# lm3414-rgb-ca-led-driver-mk-1_0.net
KiCad netlist of a schematic drawn in EAGLE
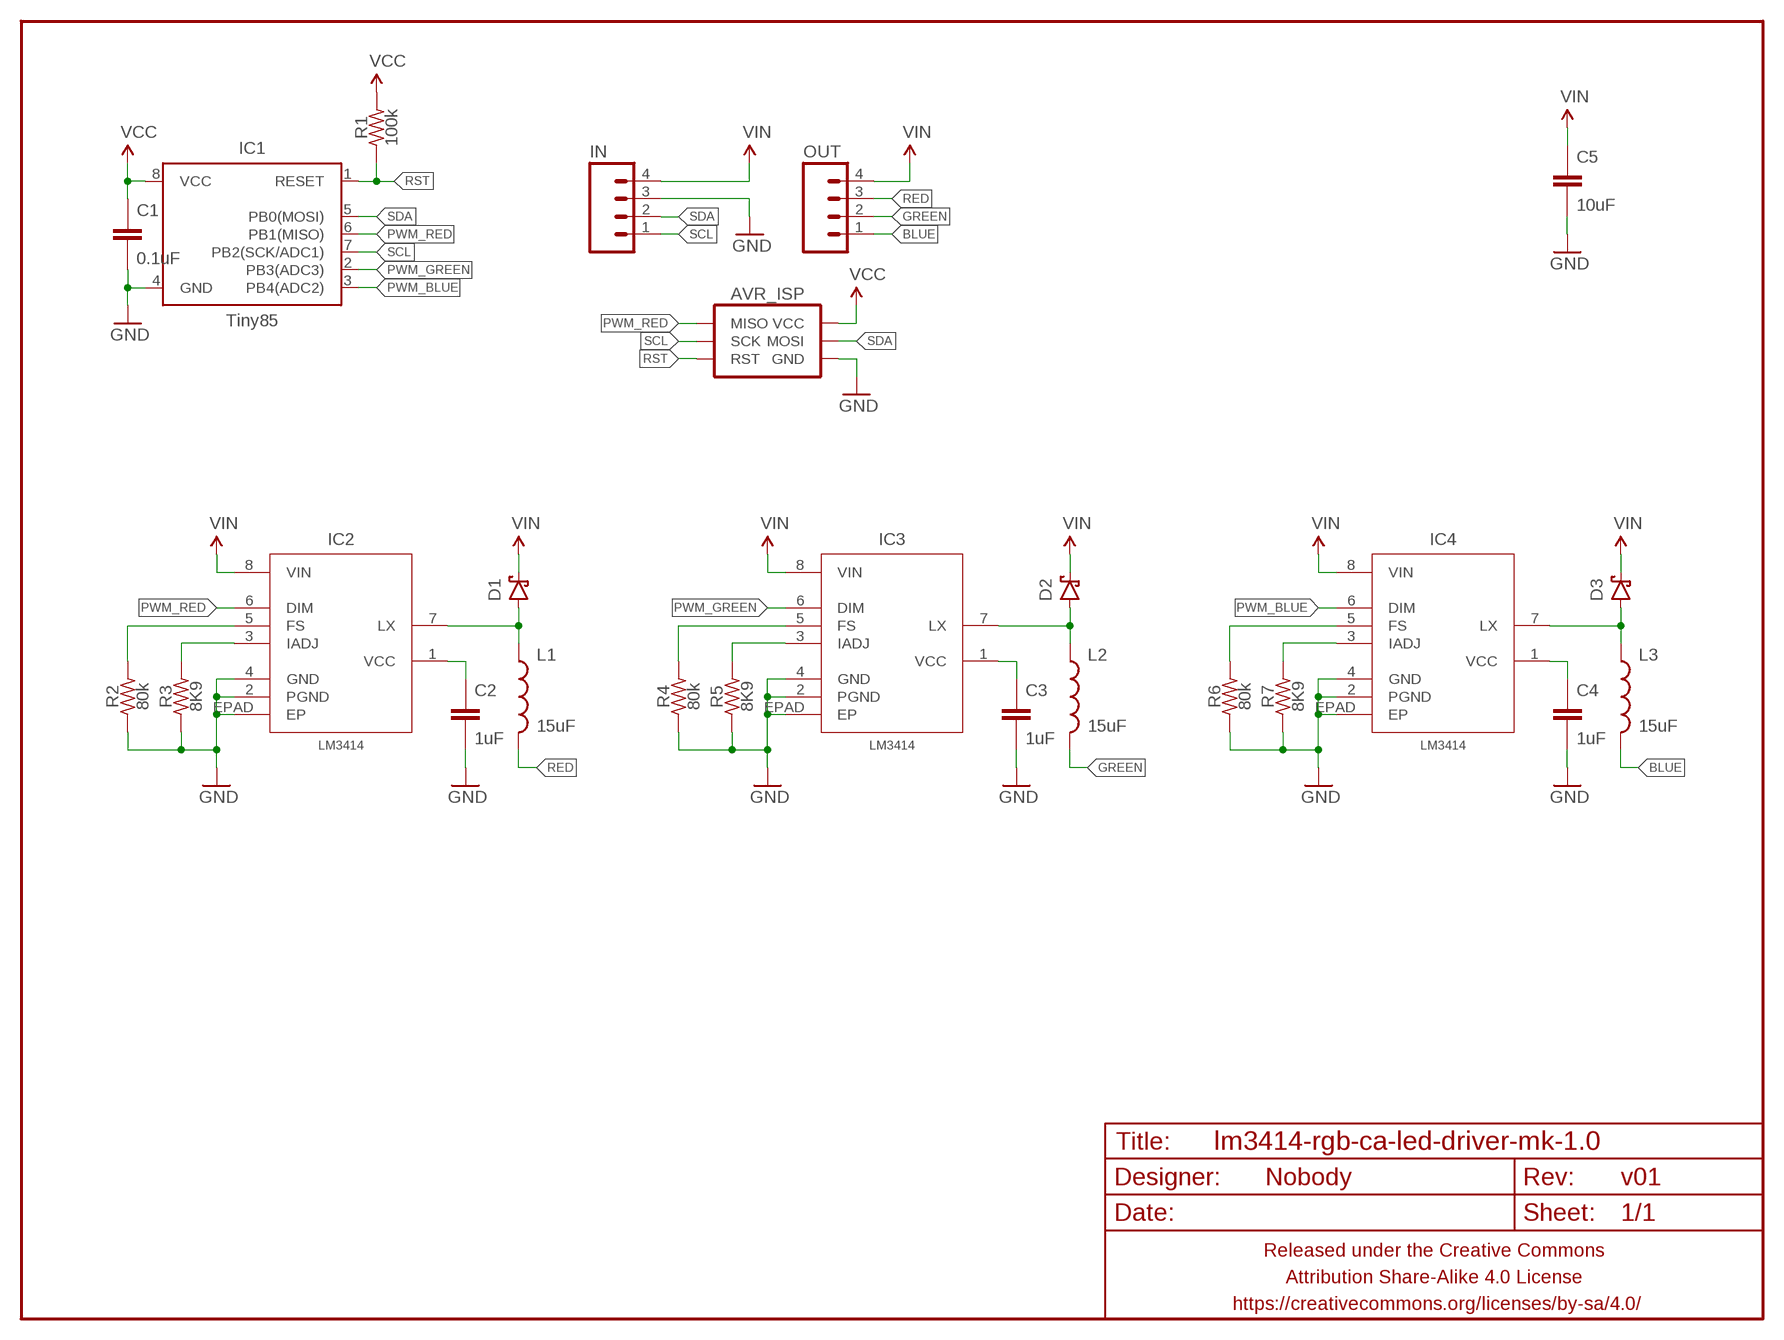
[diagram p0: schematic, sheet 1]

(export (version "E")
  (design (tool "Eeschema 10.0.6"))
  (components
    (comp (ref "AVR_ISP")
      (value "AVR_SPI_PRG_6TESTPOINTS")
      (footprint "eagle-import:2X3_TEST_POINTS")
      (libsource (lib "eagle-import") (part "AVR_SPI_PRG_6TESTPOINTS"))
    )
    (comp (ref "C1")
      (value "0.1uF")
      (footprint "eagle-import:C0603")
      (libsource (lib "eagle-import") (part "CAPACITOR-CERAMICC0603"))
    )
    (comp (ref "C2")
      (value "1uF")
      (footprint "eagle-import:C0603")
      (libsource (lib "eagle-import") (part "CAPACITOR-CERAMICC0603"))
    )
    (comp (ref "C3")
      (value "1uF")
      (footprint "eagle-import:C0603")
      (libsource (lib "eagle-import") (part "CAPACITOR-CERAMICC0603"))
    )
    (comp (ref "C4")
      (value "1uF")
      (footprint "eagle-import:C0603")
      (libsource (lib "eagle-import") (part "CAPACITOR-CERAMICC0603"))
    )
    (comp (ref "C5")
      (value "10uF")
      (footprint "eagle-import:C1206")
      (libsource (lib "eagle-import") (part "CAPACITOR-CERAMICC1206"))
    )
    (comp (ref "D1")
      (value "DIODE-SCHOTTKYSMA")
      (footprint "eagle-import:SMA-DIODE-SCHOTTKY")
      (libsource (lib "eagle-import") (part "DIODE-SCHOTTKYSMA"))
    )
    (comp (ref "D2")
      (value "DIODE-SCHOTTKYSMA")
      (footprint "eagle-import:SMA-DIODE-SCHOTTKY")
      (libsource (lib "eagle-import") (part "DIODE-SCHOTTKYSMA"))
    )
    (comp (ref "D3")
      (value "DIODE-SCHOTTKYSMA")
      (footprint "eagle-import:SMA-DIODE-SCHOTTKY")
      (libsource (lib "eagle-import") (part "DIODE-SCHOTTKYSMA"))
    )
    (comp (ref "FRAME1")
      (value "FRAME-LETTERNO_PACKAGE")
      (footprint "eagle-import:DUMMY")
      (fields (field (name "DESIGNER") "Nobody"))
      (libsource (lib "eagle-import") (part "FRAME-LETTERNO_PACKAGE"))
    )
    (comp (ref "IC1")
      (value "Tiny85")
      (footprint "eagle-import:SO08-EIAJ")
      (libsource (lib "eagle-import") (part "ATTINY45TINY85-20-SOICW"))
    )
    (comp (ref "IC2")
      (value "LM3414")
      (footprint "eagle-import:SO08-PAD")
      (libsource (lib "eagle-import") (part "LM3414SO08-PAD"))
    )
    (comp (ref "IC3")
      (value "LM3414")
      (footprint "eagle-import:SO08-PAD")
      (libsource (lib "eagle-import") (part "LM3414SO08-PAD"))
    )
    (comp (ref "IC4")
      (value "LM3414")
      (footprint "eagle-import:SO08-PAD")
      (libsource (lib "eagle-import") (part "LM3414SO08-PAD"))
    )
    (comp (ref "IN")
      (value "M04PTH")
      (footprint "eagle-import:1X04-PTH-VERT")
      (libsource (lib "eagle-import") (part "M04PTH"))
    )
    (comp (ref "L1")
      (value "15uF")
      (footprint "eagle-import:TAIYO-YUDEN-6X6X2.8")
      (libsource (lib "eagle-import") (part "INDUCTOR-TAIYO-YUDEN-6X2.8"))
    )
    (comp (ref "L2")
      (value "15uF")
      (footprint "eagle-import:TAIYO-YUDEN-6X6X2.8")
      (libsource (lib "eagle-import") (part "INDUCTOR-TAIYO-YUDEN-6X2.8"))
    )
    (comp (ref "L3")
      (value "15uF")
      (footprint "eagle-import:TAIYO-YUDEN-6X6X2.8")
      (libsource (lib "eagle-import") (part "INDUCTOR-TAIYO-YUDEN-6X2.8"))
    )
    (comp (ref "OUT")
      (value "M04PTH")
      (footprint "eagle-import:1X04-PTH-VERT")
      (libsource (lib "eagle-import") (part "M04PTH"))
    )
    (comp (ref "R1")
      (value "100k")
      (footprint "eagle-import:R0603")
      (libsource (lib "eagle-import") (part "RESISTORR0603"))
    )
    (comp (ref "R2")
      (value "80k")
      (footprint "eagle-import:R0603")
      (libsource (lib "eagle-import") (part "RESISTORR0603"))
    )
    (comp (ref "R3")
      (value "8K9")
      (footprint "eagle-import:R0603")
      (libsource (lib "eagle-import") (part "RESISTORR0603"))
    )
    (comp (ref "R4")
      (value "80k")
      (footprint "eagle-import:R0603")
      (libsource (lib "eagle-import") (part "RESISTORR0603"))
    )
    (comp (ref "R5")
      (value "8K9")
      (footprint "eagle-import:R0603")
      (libsource (lib "eagle-import") (part "RESISTORR0603"))
    )
    (comp (ref "R6")
      (value "80k")
      (footprint "eagle-import:R0603")
      (libsource (lib "eagle-import") (part "RESISTORR0603"))
    )
    (comp (ref "R7")
      (value "8K9")
      (footprint "eagle-import:R0603")
      (libsource (lib "eagle-import") (part "RESISTORR0603"))
    )
  )
  (nets
    (net (code "1") (name "BLUE") (class "Default")
      (node (ref "L3") (pin "2") (pinfunction "2_2") (pintype "passive"))
      (node (ref "OUT") (pin "1") (pinfunction "1_1") (pintype "passive"))
    )
    (net (code "2") (name "GND") (class "Default")
      (node (ref "AVR_ISP") (pin "6") (pinfunction "GND_6") (pintype "passive"))
      (node (ref "C1") (pin "2") (pinfunction "2_2") (pintype "passive"))
      (node (ref "C2") (pin "2") (pinfunction "2_2") (pintype "passive"))
      (node (ref "C3") (pin "2") (pinfunction "2_2") (pintype "passive"))
      (node (ref "C4") (pin "2") (pinfunction "2_2") (pintype "passive"))
      (node (ref "C5") (pin "2") (pinfunction "2_2") (pintype "passive"))
      (node (ref "IC1") (pin "4") (pinfunction "GND_4") (pintype "bidirectional"))
      (node (ref "IC2") (pin "2") (pinfunction "PGND_2") (pintype "bidirectional"))
      (node (ref "IC2") (pin "4") (pinfunction "GND_4") (pintype "bidirectional"))
      (node (ref "IC2") (pin "EPAD") (pinfunction "EP_EPAD") (pintype "bidirectional"))
      (node (ref "IC3") (pin "2") (pinfunction "PGND_2") (pintype "bidirectional"))
      (node (ref "IC3") (pin "4") (pinfunction "GND_4") (pintype "bidirectional"))
      (node (ref "IC3") (pin "EPAD") (pinfunction "EP_EPAD") (pintype "bidirectional"))
      (node (ref "IC4") (pin "2") (pinfunction "PGND_2") (pintype "bidirectional"))
      (node (ref "IC4") (pin "4") (pinfunction "GND_4") (pintype "bidirectional"))
      (node (ref "IC4") (pin "EPAD") (pinfunction "EP_EPAD") (pintype "bidirectional"))
      (node (ref "IN") (pin "3") (pinfunction "3_3") (pintype "passive"))
      (node (ref "R2") (pin "1") (pinfunction "1_1") (pintype "passive"))
      (node (ref "R3") (pin "1") (pinfunction "1_1") (pintype "passive"))
      (node (ref "R4") (pin "1") (pinfunction "1_1") (pintype "passive"))
      (node (ref "R5") (pin "1") (pinfunction "1_1") (pintype "passive"))
      (node (ref "R6") (pin "1") (pinfunction "1_1") (pintype "passive"))
      (node (ref "R7") (pin "1") (pinfunction "1_1") (pintype "passive"))
    )
    (net (code "3") (name "GREEN") (class "Default")
      (node (ref "L2") (pin "2") (pinfunction "2_2") (pintype "passive"))
      (node (ref "OUT") (pin "2") (pinfunction "2_2") (pintype "passive"))
    )
    (net (code "4") (name "Net-(IC2-FS)") (class "Default")
      (node (ref "IC2") (pin "5") (pinfunction "FS_5") (pintype "bidirectional"))
      (node (ref "R2") (pin "2") (pinfunction "2_2") (pintype "passive"))
    )
    (net (code "5") (name "Net-(IC2-IADJ)") (class "Default")
      (node (ref "IC2") (pin "3") (pinfunction "IADJ_3") (pintype "bidirectional"))
      (node (ref "R3") (pin "2") (pinfunction "2_2") (pintype "passive"))
    )
    (net (code "6") (name "Net-(IC2-LX)") (class "Default")
      (node (ref "D1") (pin "A") (pinfunction "A_A") (pintype "passive"))
      (node (ref "IC2") (pin "7") (pinfunction "LX_7") (pintype "bidirectional"))
      (node (ref "L1") (pin "1") (pinfunction "1_1") (pintype "passive"))
    )
    (net (code "7") (name "Net-(IC2-VCC)") (class "Default")
      (node (ref "C2") (pin "1") (pinfunction "1_1") (pintype "passive"))
      (node (ref "IC2") (pin "1") (pinfunction "VCC_1") (pintype "bidirectional"))
    )
    (net (code "8") (name "Net-(IC3-FS)") (class "Default")
      (node (ref "IC3") (pin "5") (pinfunction "FS_5") (pintype "bidirectional"))
      (node (ref "R4") (pin "2") (pinfunction "2_2") (pintype "passive"))
    )
    (net (code "9") (name "Net-(IC3-IADJ)") (class "Default")
      (node (ref "IC3") (pin "3") (pinfunction "IADJ_3") (pintype "bidirectional"))
      (node (ref "R5") (pin "2") (pinfunction "2_2") (pintype "passive"))
    )
    (net (code "10") (name "Net-(IC3-LX)") (class "Default")
      (node (ref "D2") (pin "A") (pinfunction "A_A") (pintype "passive"))
      (node (ref "IC3") (pin "7") (pinfunction "LX_7") (pintype "bidirectional"))
      (node (ref "L2") (pin "1") (pinfunction "1_1") (pintype "passive"))
    )
    (net (code "11") (name "Net-(IC3-VCC)") (class "Default")
      (node (ref "C3") (pin "1") (pinfunction "1_1") (pintype "passive"))
      (node (ref "IC3") (pin "1") (pinfunction "VCC_1") (pintype "bidirectional"))
    )
    (net (code "12") (name "Net-(IC4-FS)") (class "Default")
      (node (ref "IC4") (pin "5") (pinfunction "FS_5") (pintype "bidirectional"))
      (node (ref "R6") (pin "2") (pinfunction "2_2") (pintype "passive"))
    )
    (net (code "13") (name "Net-(IC4-IADJ)") (class "Default")
      (node (ref "IC4") (pin "3") (pinfunction "IADJ_3") (pintype "bidirectional"))
      (node (ref "R7") (pin "2") (pinfunction "2_2") (pintype "passive"))
    )
    (net (code "14") (name "Net-(IC4-LX)") (class "Default")
      (node (ref "D3") (pin "A") (pinfunction "A_A") (pintype "passive"))
      (node (ref "IC4") (pin "7") (pinfunction "LX_7") (pintype "bidirectional"))
      (node (ref "L3") (pin "1") (pinfunction "1_1") (pintype "passive"))
    )
    (net (code "15") (name "Net-(IC4-VCC)") (class "Default")
      (node (ref "C4") (pin "1") (pinfunction "1_1") (pintype "passive"))
      (node (ref "IC4") (pin "1") (pinfunction "VCC_1") (pintype "bidirectional"))
    )
    (net (code "16") (name "PWM_BLUE") (class "Default")
      (node (ref "IC1") (pin "3") (pinfunction "PB4(ADC2)_3") (pintype "bidirectional"))
      (node (ref "IC4") (pin "6") (pinfunction "DIM_6") (pintype "bidirectional"))
    )
    (net (code "17") (name "PWM_GREEN") (class "Default")
      (node (ref "IC1") (pin "2") (pinfunction "PB3(ADC3)_2") (pintype "bidirectional"))
      (node (ref "IC3") (pin "6") (pinfunction "DIM_6") (pintype "bidirectional"))
    )
    (net (code "18") (name "PWM_RED") (class "Default")
      (node (ref "AVR_ISP") (pin "1") (pinfunction "MISO_1") (pintype "passive"))
      (node (ref "IC1") (pin "6") (pinfunction "PB1(MISO)_6") (pintype "bidirectional"))
      (node (ref "IC2") (pin "6") (pinfunction "DIM_6") (pintype "bidirectional"))
    )
    (net (code "19") (name "RED") (class "Default")
      (node (ref "L1") (pin "2") (pinfunction "2_2") (pintype "passive"))
      (node (ref "OUT") (pin "3") (pinfunction "3_3") (pintype "passive"))
    )
    (net (code "20") (name "RST") (class "Default")
      (node (ref "AVR_ISP") (pin "5") (pinfunction "RST_5") (pintype "passive"))
      (node (ref "IC1") (pin "1") (pinfunction "RESET_1") (pintype "bidirectional"))
      (node (ref "R1") (pin "1") (pinfunction "1_1") (pintype "passive"))
    )
    (net (code "21") (name "SCL") (class "Default")
      (node (ref "AVR_ISP") (pin "3") (pinfunction "SCK_3") (pintype "passive"))
      (node (ref "IC1") (pin "7") (pinfunction "PB2(SCK/ADC1)_7") (pintype "bidirectional"))
      (node (ref "IN") (pin "1") (pinfunction "1_1") (pintype "passive"))
    )
    (net (code "22") (name "SDA") (class "Default")
      (node (ref "AVR_ISP") (pin "4") (pinfunction "MOSI_4") (pintype "passive"))
      (node (ref "IC1") (pin "5") (pinfunction "PB0(MOSI)_5") (pintype "bidirectional"))
      (node (ref "IN") (pin "2") (pinfunction "2_2") (pintype "passive"))
    )
    (net (code "23") (name "VCC") (class "Default")
      (node (ref "AVR_ISP") (pin "2") (pinfunction "VCC_2") (pintype "passive"))
      (node (ref "C1") (pin "1") (pinfunction "1_1") (pintype "passive"))
      (node (ref "IC1") (pin "8") (pinfunction "VCC_8") (pintype "bidirectional"))
      (node (ref "R1") (pin "2") (pinfunction "2_2") (pintype "passive"))
    )
    (net (code "24") (name "VIN") (class "Default")
      (node (ref "C5") (pin "1") (pinfunction "1_1") (pintype "passive"))
      (node (ref "D1") (pin "C") (pinfunction "C_C") (pintype "passive"))
      (node (ref "D2") (pin "C") (pinfunction "C_C") (pintype "passive"))
      (node (ref "D3") (pin "C") (pinfunction "C_C") (pintype "passive"))
      (node (ref "IC2") (pin "8") (pinfunction "VIN_8") (pintype "bidirectional"))
      (node (ref "IC3") (pin "8") (pinfunction "VIN_8") (pintype "bidirectional"))
      (node (ref "IC4") (pin "8") (pinfunction "VIN_8") (pintype "bidirectional"))
      (node (ref "IN") (pin "4") (pinfunction "4_4") (pintype "passive"))
      (node (ref "OUT") (pin "4") (pinfunction "4_4") (pintype "passive"))
    )
  )
)
